# temporizador_rev1.net
KiCad netlist of a schematic drawn in EAGLE
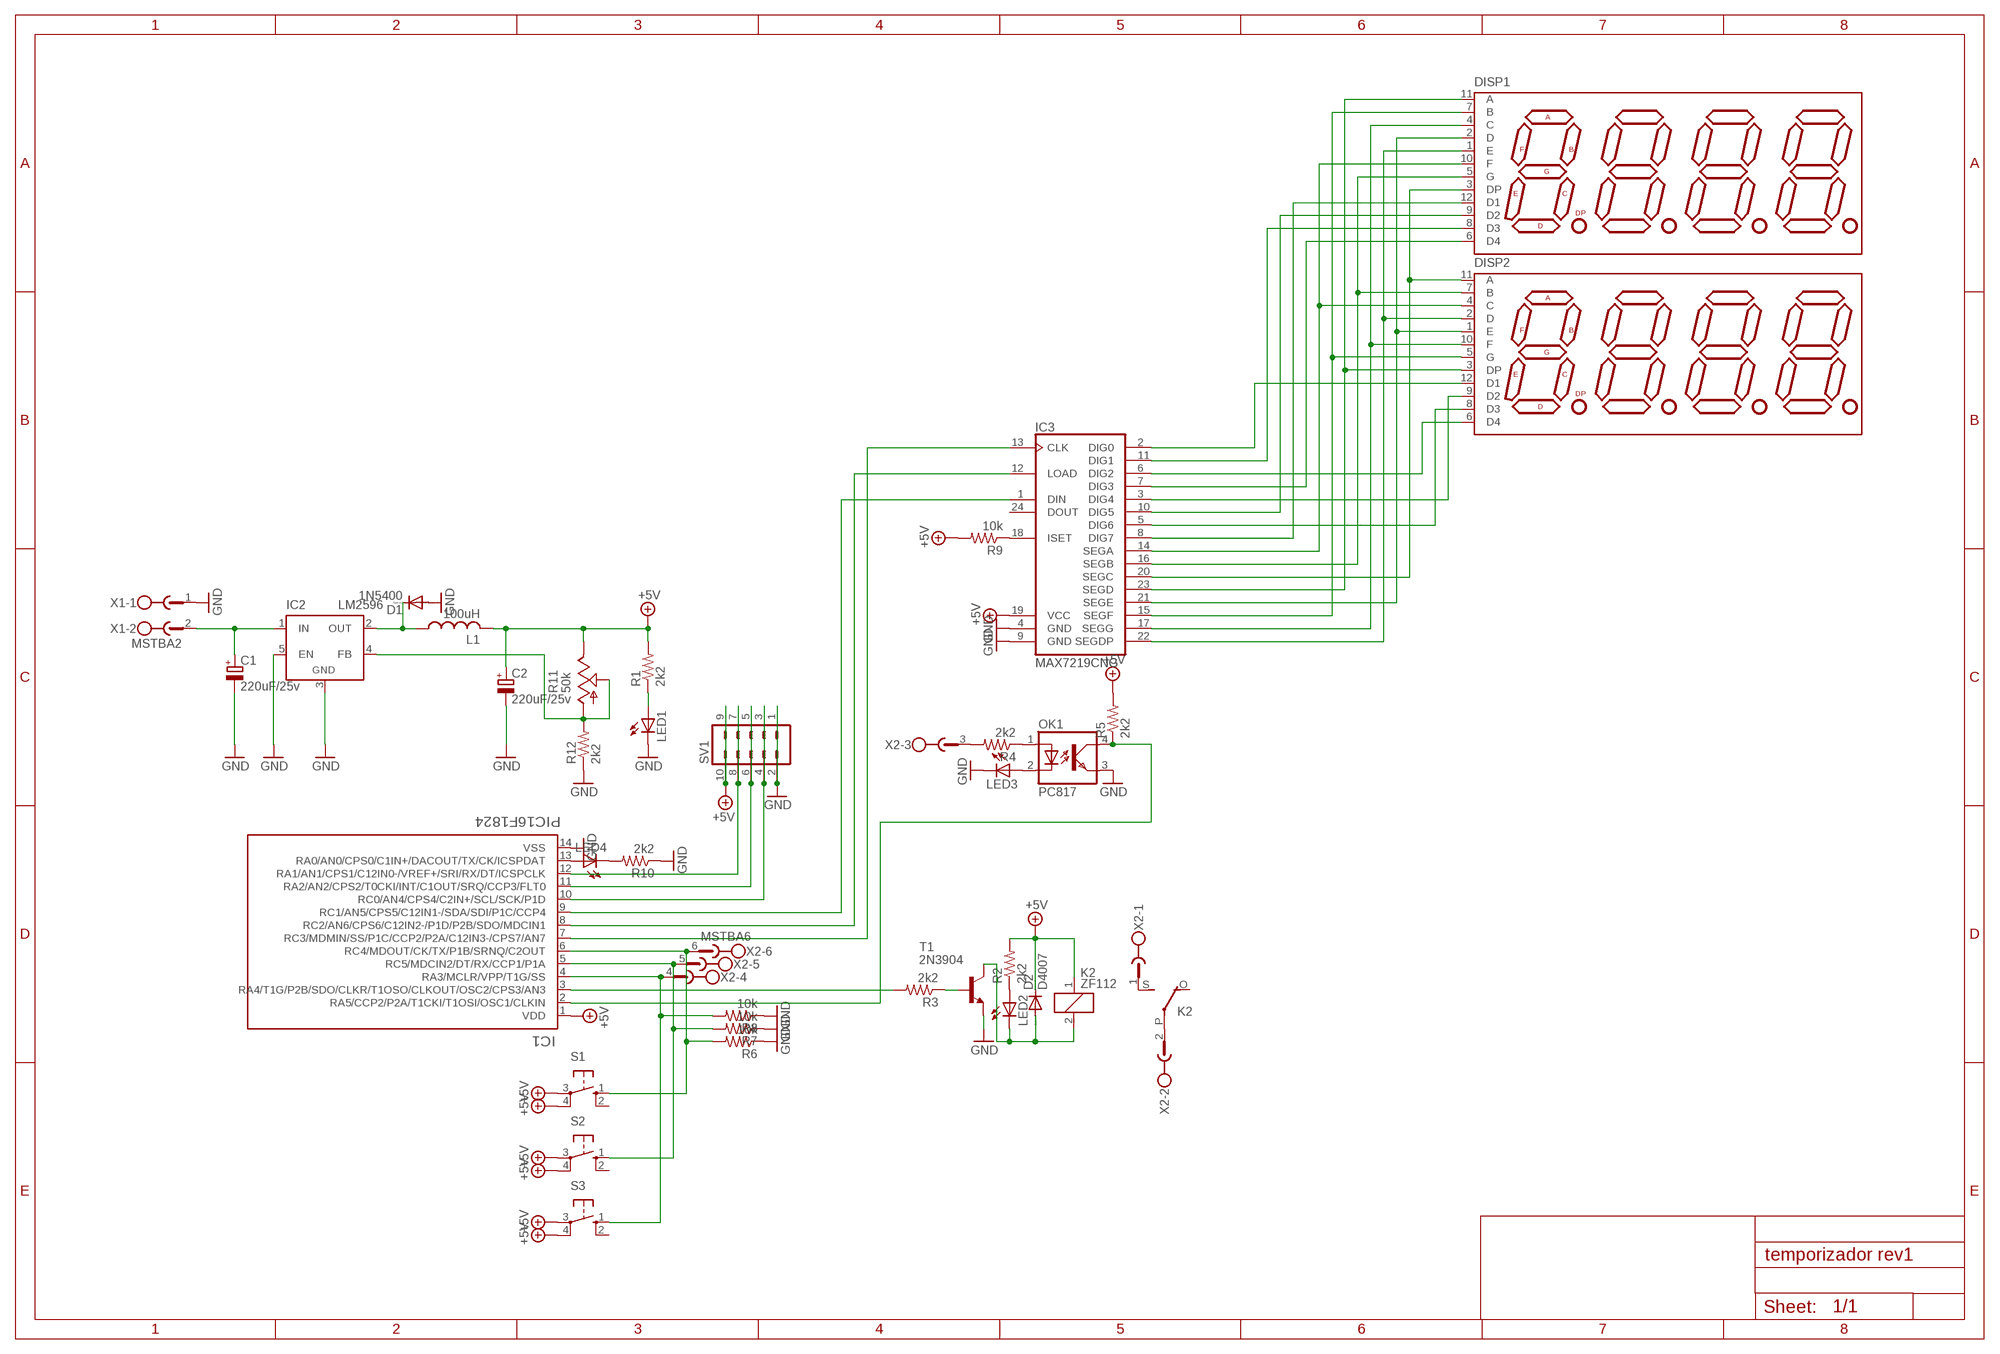
[diagram p0: schematic, sheet 1]

(export (version "E")
  (design (tool "Eeschema 10.0.6"))
  (components
    (comp (ref "C1")
      (value "220uF/25v")
      (footprint "eagle-import:E3,5-10")
      (libsource (lib "eagle-import") (part "CPOL-EUE3.5-10"))
    )
    (comp (ref "C2")
      (value "220uF/25v")
      (footprint "eagle-import:E3,5-10")
      (libsource (lib "eagle-import") (part "CPOL-EUE3.5-10"))
    )
    (comp (ref "D1")
      (value "1N5400")
      (footprint "eagle-import:DO201-15")
      (libsource (lib "eagle-import") (part "1N5400"))
    )
    (comp (ref "D2")
      (value "D4007")
      (footprint "eagle-import:DO35-10")
      (libsource (lib "eagle-import") (part "1N4148DO35-10"))
    )
    (comp (ref "DISP1")
      (value "DISP_7SEG_4DIG")
      (footprint "eagle-import:DISP_7SEG_4DIG")
      (libsource (lib "eagle-import") (part "DISP_7SEG_4DIG"))
    )
    (comp (ref "DISP2")
      (value "DISP_7SEG_4DIG")
      (footprint "eagle-import:DISP_7SEG_4DIG")
      (libsource (lib "eagle-import") (part "DISP_7SEG_4DIG"))
    )
    (comp (ref "IC1")
      (value "PIC16F1824")
      (footprint "eagle-import:PDIP14_300MC")
      (libsource (lib "eagle-import") (part "PIC16F1824"))
    )
    (comp (ref "IC2")
      (value "LM2596")
      (footprint "eagle-import:TO220-51")
      (libsource (lib "eagle-import") (part "LM2596TV"))
    )
    (comp (ref "IC3")
      (value "MAX7219CNG")
      (footprint "eagle-import:DIL24-3")
      (fields (field (name "MF") "MAXIM"))
      (libsource (lib "eagle-import") (part "MAX7219CNG"))
    )
    (comp (ref "K2")
      (value "ZF112")
      (footprint "eagle-import:ZF112")
      (libsource (lib "eagle-import") (part "ZF112"))
    )
    (comp (ref "L1")
      (value "100uH")
      (footprint "eagle-import:6000-XXXX-RC")
      (libsource (lib "eagle-import") (part "L-US6000-XXX-RC"))
    )
    (comp (ref "LED1")
      (value "LED3MM")
      (footprint "eagle-import:LED3MM")
      (libsource (lib "eagle-import") (part "LED3MM"))
    )
    (comp (ref "LED2")
      (value "LED3MM")
      (footprint "eagle-import:LED3MM")
      (libsource (lib "eagle-import") (part "LED3MM"))
    )
    (comp (ref "LED3")
      (value "LED3MM")
      (footprint "eagle-import:LED3MM")
      (libsource (lib "eagle-import") (part "LED3MM"))
    )
    (comp (ref "LED4")
      (value "LED3MM")
      (footprint "eagle-import:LED3MM")
      (libsource (lib "eagle-import") (part "LED3MM"))
    )
    (comp (ref "OK1")
      (value "PC817")
      (footprint "eagle-import:DIL04")
      (fields (field (name "MPN") "PC817X4J000F"))
      (libsource (lib "eagle-import") (part "PC817"))
    )
    (comp (ref "R1")
      (value "2k2")
      (footprint "eagle-import:0207_10")
      (libsource (lib "eagle-import") (part "R-US_0207/10"))
    )
    (comp (ref "R2")
      (value "2k2")
      (footprint "eagle-import:0207_10")
      (libsource (lib "eagle-import") (part "R-US_0207/10"))
    )
    (comp (ref "R3")
      (value "2k2")
      (footprint "eagle-import:0207_10")
      (libsource (lib "eagle-import") (part "R-US_0207/10"))
    )
    (comp (ref "R4")
      (value "2k2")
      (footprint "eagle-import:0207_10")
      (libsource (lib "eagle-import") (part "R-US_0207/10"))
    )
    (comp (ref "R5")
      (value "2k2")
      (footprint "eagle-import:0207_10")
      (libsource (lib "eagle-import") (part "R-US_0207/10"))
    )
    (comp (ref "R6")
      (value "10k")
      (footprint "eagle-import:0207_10")
      (libsource (lib "eagle-import") (part "R-US_0207/10"))
    )
    (comp (ref "R7")
      (value "10k")
      (footprint "eagle-import:0207_10")
      (libsource (lib "eagle-import") (part "R-US_0207/10"))
    )
    (comp (ref "R8")
      (value "10k")
      (footprint "eagle-import:0207_10")
      (libsource (lib "eagle-import") (part "R-US_0207/10"))
    )
    (comp (ref "R9")
      (value "10k")
      (footprint "eagle-import:R0805")
      (libsource (lib "eagle-import") (part "R-US_R0805"))
    )
    (comp (ref "R10")
      (value "2k2")
      (footprint "eagle-import:0207_10")
      (libsource (lib "eagle-import") (part "R-US_0207/10"))
    )
    (comp (ref "R11")
      (value "50k")
      (footprint "eagle-import:B25P")
      (libsource (lib "eagle-import") (part "TRIM_US-B25P"))
    )
    (comp (ref "R12")
      (value "2k2")
      (footprint "eagle-import:0207_10")
      (libsource (lib "eagle-import") (part "R-US_0207/10"))
    )
    (comp (ref "S1")
      (value "10-XX")
      (footprint "eagle-import:B3F-10XX")
      (fields (field (name "MPN") "B3F-1000"))
      (libsource (lib "eagle-import") (part "10-XX"))
    )
    (comp (ref "S2")
      (value "10-XX")
      (footprint "eagle-import:B3F-10XX")
      (fields (field (name "MPN") "B3F-1000"))
      (libsource (lib "eagle-import") (part "10-XX"))
    )
    (comp (ref "S3")
      (value "10-XX")
      (footprint "eagle-import:B3F-10XX")
      (fields (field (name "MPN") "B3F-1000"))
      (libsource (lib "eagle-import") (part "10-XX"))
    )
    (comp (ref "SV1")
      (value "MA05-2")
      (footprint "eagle-import:MA05-2")
      (libsource (lib "eagle-import") (part "MA05-2"))
    )
    (comp (ref "T1")
      (value "2N3904")
      (footprint "eagle-import:TO92-EBC")
      (libsource (lib "eagle-import") (part "-NPN-TO92-EBC2N3904"))
    )
    (comp (ref "X1")
      (value "MSTBA2")
      (footprint "eagle-import:MSTBA2")
      (fields (field (name "MF") "FARNELL") (field (name "MPN") "1757242"))
      (libsource (lib "eagle-import") (part "MSTBA2"))
    )
    (comp (ref "X2")
      (value "MSTBA6")
      (footprint "eagle-import:MSTBA6")
      (fields (field (name "MF") "FARNELL") (field (name "MPN") "1757284"))
      (libsource (lib "eagle-import") (part "MSTBA6"))
    )
  )
  (nets
    (net (code "1") (name "+5V") (class "Default")
      (node (ref "C2") (pin "+") (pinfunction "+_+") (pintype "passive"))
      (node (ref "D2") (pin "C") (pinfunction "C_C") (pintype "passive"))
      (node (ref "IC1") (pin "1") (pinfunction "VDD_1") (pintype "power_in"))
      (node (ref "IC3") (pin "19") (pinfunction "VCC_19") (pintype "power_in"))
      (node (ref "K2") (pin "1") (pinfunction "1_1") (pintype "passive"))
      (node (ref "L1") (pin "2") (pinfunction "2_2") (pintype "passive"))
      (node (ref "R1") (pin "2") (pinfunction "2_2") (pintype "passive"))
      (node (ref "R11") (pin "E") (pinfunction "E_E") (pintype "passive"))
      (node (ref "R2") (pin "2") (pinfunction "2_2") (pintype "passive"))
      (node (ref "R5") (pin "2") (pinfunction "2_2") (pintype "passive"))
      (node (ref "R9") (pin "2") (pinfunction "2_2") (pintype "passive"))
      (node (ref "S1") (pin "3") (pinfunction "P_3") (pintype "passive"))
      (node (ref "S1") (pin "4") (pinfunction "P1_4") (pintype "passive"))
      (node (ref "S2") (pin "3") (pinfunction "P_3") (pintype "passive"))
      (node (ref "S2") (pin "4") (pinfunction "P1_4") (pintype "passive"))
      (node (ref "S3") (pin "3") (pinfunction "P_3") (pintype "passive"))
      (node (ref "S3") (pin "4") (pinfunction "P1_4") (pintype "passive"))
      (node (ref "SV1") (pin "10") (pinfunction "10_10") (pintype "passive"))
      (node (ref "SV1") (pin "9") (pinfunction "9_9") (pintype "passive"))
    )
    (net (code "2") (name "GND") (class "Default")
      (node (ref "C1") (pin "-") (pinfunction "-_-") (pintype "passive"))
      (node (ref "C2") (pin "-") (pinfunction "-_-") (pintype "passive"))
      (node (ref "D1") (pin "A") (pinfunction "A_A") (pintype "passive"))
      (node (ref "IC1") (pin "14") (pinfunction "VSS_14") (pintype "power_in"))
      (node (ref "IC2") (pin "3") (pinfunction "GND_3") (pintype "power_in"))
      (node (ref "IC2") (pin "5") (pinfunction "EN_5") (pintype "input"))
      (node (ref "IC3") (pin "4") (pinfunction "GND_4") (pintype "power_in"))
      (node (ref "IC3") (pin "9") (pinfunction "GND_9") (pintype "power_in"))
      (node (ref "LED1") (pin "K") (pinfunction "C_K") (pintype "passive"))
      (node (ref "LED3") (pin "K") (pinfunction "C_K") (pintype "passive"))
      (node (ref "OK1") (pin "3") (pinfunction "EMIT_3") (pintype "passive"))
      (node (ref "R10") (pin "1") (pinfunction "1_1") (pintype "passive"))
      (node (ref "R12") (pin "1") (pinfunction "1_1") (pintype "passive"))
      (node (ref "R6") (pin "1") (pinfunction "1_1") (pintype "passive"))
      (node (ref "R7") (pin "1") (pinfunction "1_1") (pintype "passive"))
      (node (ref "R8") (pin "1") (pinfunction "1_1") (pintype "passive"))
      (node (ref "SV1") (pin "1") (pinfunction "1_1") (pintype "passive"))
      (node (ref "SV1") (pin "2") (pinfunction "2_2") (pintype "passive"))
      (node (ref "T1") (pin "E") (pinfunction "E_E") (pintype "passive"))
      (node (ref "X1") (pin "1") (pinfunction "1_1") (pintype "passive"))
    )
    (net (code "3") (name "Net-(DISP1-A)") (class "Default")
      (node (ref "DISP1") (pin "11") (pinfunction "A_11") (pintype "bidirectional"))
      (node (ref "DISP2") (pin "3") (pinfunction "DP_3") (pintype "bidirectional"))
      (node (ref "IC3") (pin "23") (pinfunction "SEGD_23") (pintype "output"))
    )
    (net (code "4") (name "Net-(DISP1-B)") (class "Default")
      (node (ref "DISP1") (pin "7") (pinfunction "B_7") (pintype "bidirectional"))
      (node (ref "DISP2") (pin "5") (pinfunction "G_5") (pintype "bidirectional"))
      (node (ref "IC3") (pin "15") (pinfunction "SEGF_15") (pintype "output"))
    )
    (net (code "5") (name "Net-(DISP1-C)") (class "Default")
      (node (ref "DISP1") (pin "4") (pinfunction "C_4") (pintype "bidirectional"))
      (node (ref "DISP2") (pin "10") (pinfunction "F_10") (pintype "bidirectional"))
      (node (ref "IC3") (pin "17") (pinfunction "SEGG_17") (pintype "output"))
    )
    (net (code "6") (name "Net-(DISP1-D)") (class "Default")
      (node (ref "DISP1") (pin "2") (pinfunction "D_2") (pintype "bidirectional"))
      (node (ref "DISP2") (pin "1") (pinfunction "E_1") (pintype "bidirectional"))
      (node (ref "IC3") (pin "21") (pinfunction "SEGE_21") (pintype "output"))
    )
    (net (code "7") (name "Net-(DISP1-D1)") (class "Default")
      (node (ref "DISP1") (pin "12") (pinfunction "D1_12") (pintype "bidirectional"))
      (node (ref "IC3") (pin "8") (pinfunction "DIG7_8") (pintype "output"))
    )
    (net (code "8") (name "Net-(DISP1-D2)") (class "Default")
      (node (ref "DISP1") (pin "9") (pinfunction "D2_9") (pintype "bidirectional"))
      (node (ref "IC3") (pin "10") (pinfunction "DIG5_10") (pintype "output"))
    )
    (net (code "9") (name "Net-(DISP1-D3)") (class "Default")
      (node (ref "DISP1") (pin "8") (pinfunction "D3_8") (pintype "bidirectional"))
      (node (ref "IC3") (pin "11") (pinfunction "DIG1_11") (pintype "output"))
    )
    (net (code "10") (name "Net-(DISP1-D4)") (class "Default")
      (node (ref "DISP1") (pin "6") (pinfunction "D4_6") (pintype "bidirectional"))
      (node (ref "IC3") (pin "7") (pinfunction "DIG3_7") (pintype "output"))
    )
    (net (code "11") (name "Net-(DISP1-DP)") (class "Default")
      (node (ref "DISP1") (pin "3") (pinfunction "DP_3") (pintype "bidirectional"))
      (node (ref "DISP2") (pin "11") (pinfunction "A_11") (pintype "bidirectional"))
      (node (ref "IC3") (pin "20") (pinfunction "SEGC_20") (pintype "output"))
    )
    (net (code "12") (name "Net-(DISP1-E)") (class "Default")
      (node (ref "DISP1") (pin "1") (pinfunction "E_1") (pintype "bidirectional"))
      (node (ref "DISP2") (pin "2") (pinfunction "D_2") (pintype "bidirectional"))
      (node (ref "IC3") (pin "22") (pinfunction "SEGDP_22") (pintype "output"))
    )
    (net (code "13") (name "Net-(DISP1-F)") (class "Default")
      (node (ref "DISP1") (pin "10") (pinfunction "F_10") (pintype "bidirectional"))
      (node (ref "DISP2") (pin "4") (pinfunction "C_4") (pintype "bidirectional"))
      (node (ref "IC3") (pin "14") (pinfunction "SEGA_14") (pintype "output"))
    )
    (net (code "14") (name "Net-(DISP1-G)") (class "Default")
      (node (ref "DISP1") (pin "5") (pinfunction "G_5") (pintype "bidirectional"))
      (node (ref "DISP2") (pin "7") (pinfunction "B_7") (pintype "bidirectional"))
      (node (ref "IC3") (pin "16") (pinfunction "SEGB_16") (pintype "output"))
    )
    (net (code "15") (name "Net-(DISP2-D1)") (class "Default")
      (node (ref "DISP2") (pin "12") (pinfunction "D1_12") (pintype "bidirectional"))
      (node (ref "IC3") (pin "2") (pinfunction "DIG0_2") (pintype "output"))
    )
    (net (code "16") (name "Net-(DISP2-D2)") (class "Default")
      (node (ref "DISP2") (pin "9") (pinfunction "D2_9") (pintype "bidirectional"))
      (node (ref "IC3") (pin "3") (pinfunction "DIG4_3") (pintype "output"))
    )
    (net (code "17") (name "Net-(DISP2-D3)") (class "Default")
      (node (ref "DISP2") (pin "8") (pinfunction "D3_8") (pintype "bidirectional"))
      (node (ref "IC3") (pin "5") (pinfunction "DIG6_5") (pintype "output"))
    )
    (net (code "18") (name "Net-(DISP2-D4)") (class "Default")
      (node (ref "DISP2") (pin "6") (pinfunction "D4_6") (pintype "bidirectional"))
      (node (ref "IC3") (pin "6") (pinfunction "DIG2_6") (pintype "output"))
    )
    (net (code "19") (name "Net-(IC1-RA0{slash}AN0{slash}CPS0{slash}C1IN+{slash}DACOUT{slash}TX{slash}CK{slash}ICSPDAT)") (class "Default")
      (node (ref "IC1") (pin "13") (pinfunction "RA0/AN0/CPS0/C1IN+/DACOUT/TX/CK/ICSPDAT_13") (pintype "bidirectional"))
      (node (ref "LED4") (pin "A") (pinfunction "A_A") (pintype "passive"))
    )
    (net (code "20") (name "Net-(IC1-RA1{slash}AN1{slash}CPS1{slash}C12IN0-{slash}VREF+{slash}SRI{slash}RX{slash}DT{slash}ICSPCLK)") (class "Default")
      (node (ref "IC1") (pin "12") (pinfunction "RA1/AN1/CPS1/C12IN0-/VREF+/SRI/RX/DT/ICSPCLK_12") (pintype "bidirectional"))
      (node (ref "SV1") (pin "7") (pinfunction "7_7") (pintype "passive"))
      (node (ref "SV1") (pin "8") (pinfunction "8_8") (pintype "passive"))
    )
    (net (code "21") (name "Net-(IC1-RA2{slash}AN2{slash}CPS2{slash}T0CKI{slash}INT{slash}C1OUT{slash}SRQ{slash}CCP3{slash}FLT0)") (class "Default")
      (node (ref "IC1") (pin "11") (pinfunction "RA2/AN2/CPS2/T0CKI/INT/C1OUT/SRQ/CCP3/FLT0_11") (pintype "bidirectional"))
      (node (ref "SV1") (pin "5") (pinfunction "5_5") (pintype "passive"))
      (node (ref "SV1") (pin "6") (pinfunction "6_6") (pintype "passive"))
    )
    (net (code "22") (name "Net-(IC1-RA3{slash}MCLR{slash}VPP{slash}T1G{slash}SS)") (class "Default")
      (node (ref "IC1") (pin "4") (pinfunction "RA3/MCLR/VPP/T1G/SS_4") (pintype "bidirectional"))
      (node (ref "R8") (pin "2") (pinfunction "2_2") (pintype "passive"))
      (node (ref "S3") (pin "1") (pinfunction "S_1") (pintype "passive"))
      (node (ref "X2") (pin "4") (pinfunction "1_4") (pintype "passive"))
    )
    (net (code "23") (name "Net-(IC1-RA4{slash}T1G{slash}P2B{slash}SDO{slash}CLKR{slash}T1OSO{slash}CLKOUT{slash}OSC2{slash}CPS3{slash}AN3)") (class "Default")
      (node (ref "IC1") (pin "3") (pinfunction "RA4/T1G/P2B/SDO/CLKR/T1OSO/CLKOUT/OSC2/CPS3/AN3_3") (pintype "bidirectional"))
      (node (ref "R3") (pin "2") (pinfunction "2_2") (pintype "passive"))
    )
    (net (code "24") (name "Net-(IC1-RA5{slash}CCP2{slash}P2A{slash}T1CKI{slash}T1OSI{slash}OSC1{slash}CLKIN)") (class "Default")
      (node (ref "IC1") (pin "2") (pinfunction "RA5/CCP2/P2A/T1CKI/T1OSI/OSC1/CLKIN_2") (pintype "bidirectional"))
      (node (ref "OK1") (pin "4") (pinfunction "COL_4") (pintype "passive"))
      (node (ref "R5") (pin "1") (pinfunction "1_1") (pintype "passive"))
    )
    (net (code "25") (name "Net-(IC1-RC0{slash}AN4{slash}CPS4{slash}C2IN+{slash}SCL{slash}SCK{slash}P1D)") (class "Default")
      (node (ref "IC1") (pin "10") (pinfunction "RC0/AN4/CPS4/C2IN+/SCL/SCK/P1D_10") (pintype "bidirectional"))
      (node (ref "SV1") (pin "3") (pinfunction "3_3") (pintype "passive"))
      (node (ref "SV1") (pin "4") (pinfunction "4_4") (pintype "passive"))
    )
    (net (code "26") (name "Net-(IC1-RC1{slash}AN5{slash}CPS5{slash}C12IN1-{slash}SDA{slash}SDI{slash}P1C{slash}CCP4)") (class "Default")
      (node (ref "IC1") (pin "9") (pinfunction "RC1/AN5/CPS5/C12IN1-/SDA/SDI/P1C/CCP4_9") (pintype "bidirectional"))
      (node (ref "IC3") (pin "1") (pinfunction "DIN_1") (pintype "input"))
    )
    (net (code "27") (name "Net-(IC1-RC2{slash}AN6{slash}CPS6{slash}C12IN2-{slash}P1D{slash}P2B{slash}SDO{slash}MDCIN1)") (class "Default")
      (node (ref "IC1") (pin "8") (pinfunction "RC2/AN6/CPS6/C12IN2-/P1D/P2B/SDO/MDCIN1_8") (pintype "bidirectional"))
      (node (ref "IC3") (pin "12") (pinfunction "LOAD_12") (pintype "input"))
    )
    (net (code "28") (name "Net-(IC1-RC3{slash}MDMIN{slash}SS{slash}P1C{slash}CCP2{slash}P2A{slash}C12IN3-{slash}CPS7{slash}AN7)") (class "Default")
      (node (ref "IC1") (pin "7") (pinfunction "RC3/MDMIN/SS/P1C/CCP2/P2A/C12IN3-/CPS7/AN7_7") (pintype "bidirectional"))
      (node (ref "IC3") (pin "13") (pinfunction "CLK_13") (pintype "input"))
    )
    (net (code "29") (name "Net-(IC1-RC4{slash}MDOUT{slash}CK{slash}TX{slash}P1B{slash}SRNQ{slash}C2OUT)") (class "Default")
      (node (ref "IC1") (pin "6") (pinfunction "RC4/MDOUT/CK/TX/P1B/SRNQ/C2OUT_6") (pintype "bidirectional"))
      (node (ref "R6") (pin "2") (pinfunction "2_2") (pintype "passive"))
      (node (ref "S1") (pin "1") (pinfunction "S_1") (pintype "passive"))
      (node (ref "X2") (pin "6") (pinfunction "1_6") (pintype "passive"))
    )
    (net (code "30") (name "Net-(IC1-RC5{slash}MDCIN2{slash}DT{slash}RX{slash}CCP1{slash}P1A)") (class "Default")
      (node (ref "IC1") (pin "5") (pinfunction "RC5/MDCIN2/DT/RX/CCP1/P1A_5") (pintype "bidirectional"))
      (node (ref "R7") (pin "2") (pinfunction "2_2") (pintype "passive"))
      (node (ref "S2") (pin "1") (pinfunction "S_1") (pintype "passive"))
      (node (ref "X2") (pin "5") (pinfunction "1_5") (pintype "passive"))
    )
    (net (code "31") (name "Net-(IC2-FB)") (class "Default")
      (node (ref "IC2") (pin "4") (pinfunction "FB_4") (pintype "input"))
      (node (ref "R11") (pin "A") (pinfunction "A_A") (pintype "passive"))
      (node (ref "R11") (pin "S") (pinfunction "S_S") (pintype "passive"))
      (node (ref "R12") (pin "2") (pinfunction "2_2") (pintype "passive"))
    )
    (net (code "32") (name "Net-(IC2-IN)") (class "Default")
      (node (ref "C1") (pin "+") (pinfunction "+_+") (pintype "passive"))
      (node (ref "IC2") (pin "1") (pinfunction "IN_1") (pintype "input"))
      (node (ref "X1") (pin "2") (pinfunction "1_2") (pintype "passive"))
    )
    (net (code "33") (name "Net-(IC2-OUT)") (class "Default")
      (node (ref "D1") (pin "C") (pinfunction "C_C") (pintype "passive"))
      (node (ref "IC2") (pin "2") (pinfunction "OUT_2") (pintype "output"))
      (node (ref "L1") (pin "1") (pinfunction "1_1") (pintype "passive"))
    )
    (net (code "34") (name "Net-(IC3-ISET)") (class "Default")
      (node (ref "IC3") (pin "18") (pinfunction "ISET_18") (pintype "input"))
      (node (ref "R9") (pin "1") (pinfunction "1_1") (pintype "passive"))
    )
    (net (code "35") (name "Net-(K2-PadS)") (class "Default")
      (node (ref "K2") (pin "S") (pinfunction "S_S") (pintype "passive"))
      (node (ref "X2") (pin "1") (pinfunction "1_1") (pintype "passive"))
    )
    (net (code "36") (name "Net-(LED1-PadA)") (class "Default")
      (node (ref "LED1") (pin "A") (pinfunction "A_A") (pintype "passive"))
      (node (ref "R1") (pin "1") (pinfunction "1_1") (pintype "passive"))
    )
    (net (code "37") (name "Net-(LED2-C)") (class "Default")
      (node (ref "D2") (pin "A") (pinfunction "A_A") (pintype "passive"))
      (node (ref "K2") (pin "2") (pinfunction "2_2") (pintype "passive"))
      (node (ref "LED2") (pin "K") (pinfunction "C_K") (pintype "passive"))
      (node (ref "T1") (pin "C") (pinfunction "C_C") (pintype "passive"))
    )
    (net (code "38") (name "Net-(LED2-PadA)") (class "Default")
      (node (ref "LED2") (pin "A") (pinfunction "A_A") (pintype "passive"))
      (node (ref "R2") (pin "1") (pinfunction "1_1") (pintype "passive"))
    )
    (net (code "39") (name "Net-(LED4-C)") (class "Default")
      (node (ref "LED4") (pin "K") (pinfunction "C_K") (pintype "passive"))
      (node (ref "R10") (pin "2") (pinfunction "2_2") (pintype "passive"))
    )
    (net (code "40") (name "Net-(OK1-A)") (class "Default")
      (node (ref "OK1") (pin "1") (pinfunction "A_1") (pintype "passive"))
      (node (ref "R4") (pin "1") (pinfunction "1_1") (pintype "passive"))
    )
    (net (code "41") (name "Net-(OK1-C)") (class "Default")
      (node (ref "LED3") (pin "A") (pinfunction "A_A") (pintype "passive"))
      (node (ref "OK1") (pin "2") (pinfunction "C_2") (pintype "passive"))
    )
    (net (code "42") (name "Net-(R3-Pad1)") (class "Default")
      (node (ref "R3") (pin "1") (pinfunction "1_1") (pintype "passive"))
      (node (ref "T1") (pin "B") (pinfunction "B_B") (pintype "passive"))
    )
    (net (code "43") (name "Net-(X2B-1)") (class "Default")
      (node (ref "K2") (pin "P") (pinfunction "P_P") (pintype "passive"))
      (node (ref "X2") (pin "2") (pinfunction "1_2") (pintype "passive"))
    )
    (net (code "44") (name "Net-(X2C-1)") (class "Default")
      (node (ref "R4") (pin "2") (pinfunction "2_2") (pintype "passive"))
      (node (ref "X2") (pin "3") (pinfunction "1_3") (pintype "passive"))
    )
    (net (code "45") (name "unconnected-(IC3-DOUT-Pad24)") (class "Default")
      (node (ref "IC3") (pin "24") (pinfunction "DOUT_24") (pintype "output"))
    )
    (net (code "46") (name "unconnected-(K2-PadO)") (class "Default")
      (node (ref "K2") (pin "O") (pinfunction "O_O") (pintype "passive"))
    )
    (net (code "47") (name "unconnected-(S1-S1-Pad2)") (class "Default")
      (node (ref "S1") (pin "2") (pinfunction "S1_2") (pintype "passive"))
    )
    (net (code "48") (name "unconnected-(S2-S1-Pad2)") (class "Default")
      (node (ref "S2") (pin "2") (pinfunction "S1_2") (pintype "passive"))
    )
    (net (code "49") (name "unconnected-(S3-S1-Pad2)") (class "Default")
      (node (ref "S3") (pin "2") (pinfunction "S1_2") (pintype "passive"))
    )
  )
)
